# Retro_Watch.net
KiCad netlist of a schematic drawn in EAGLE
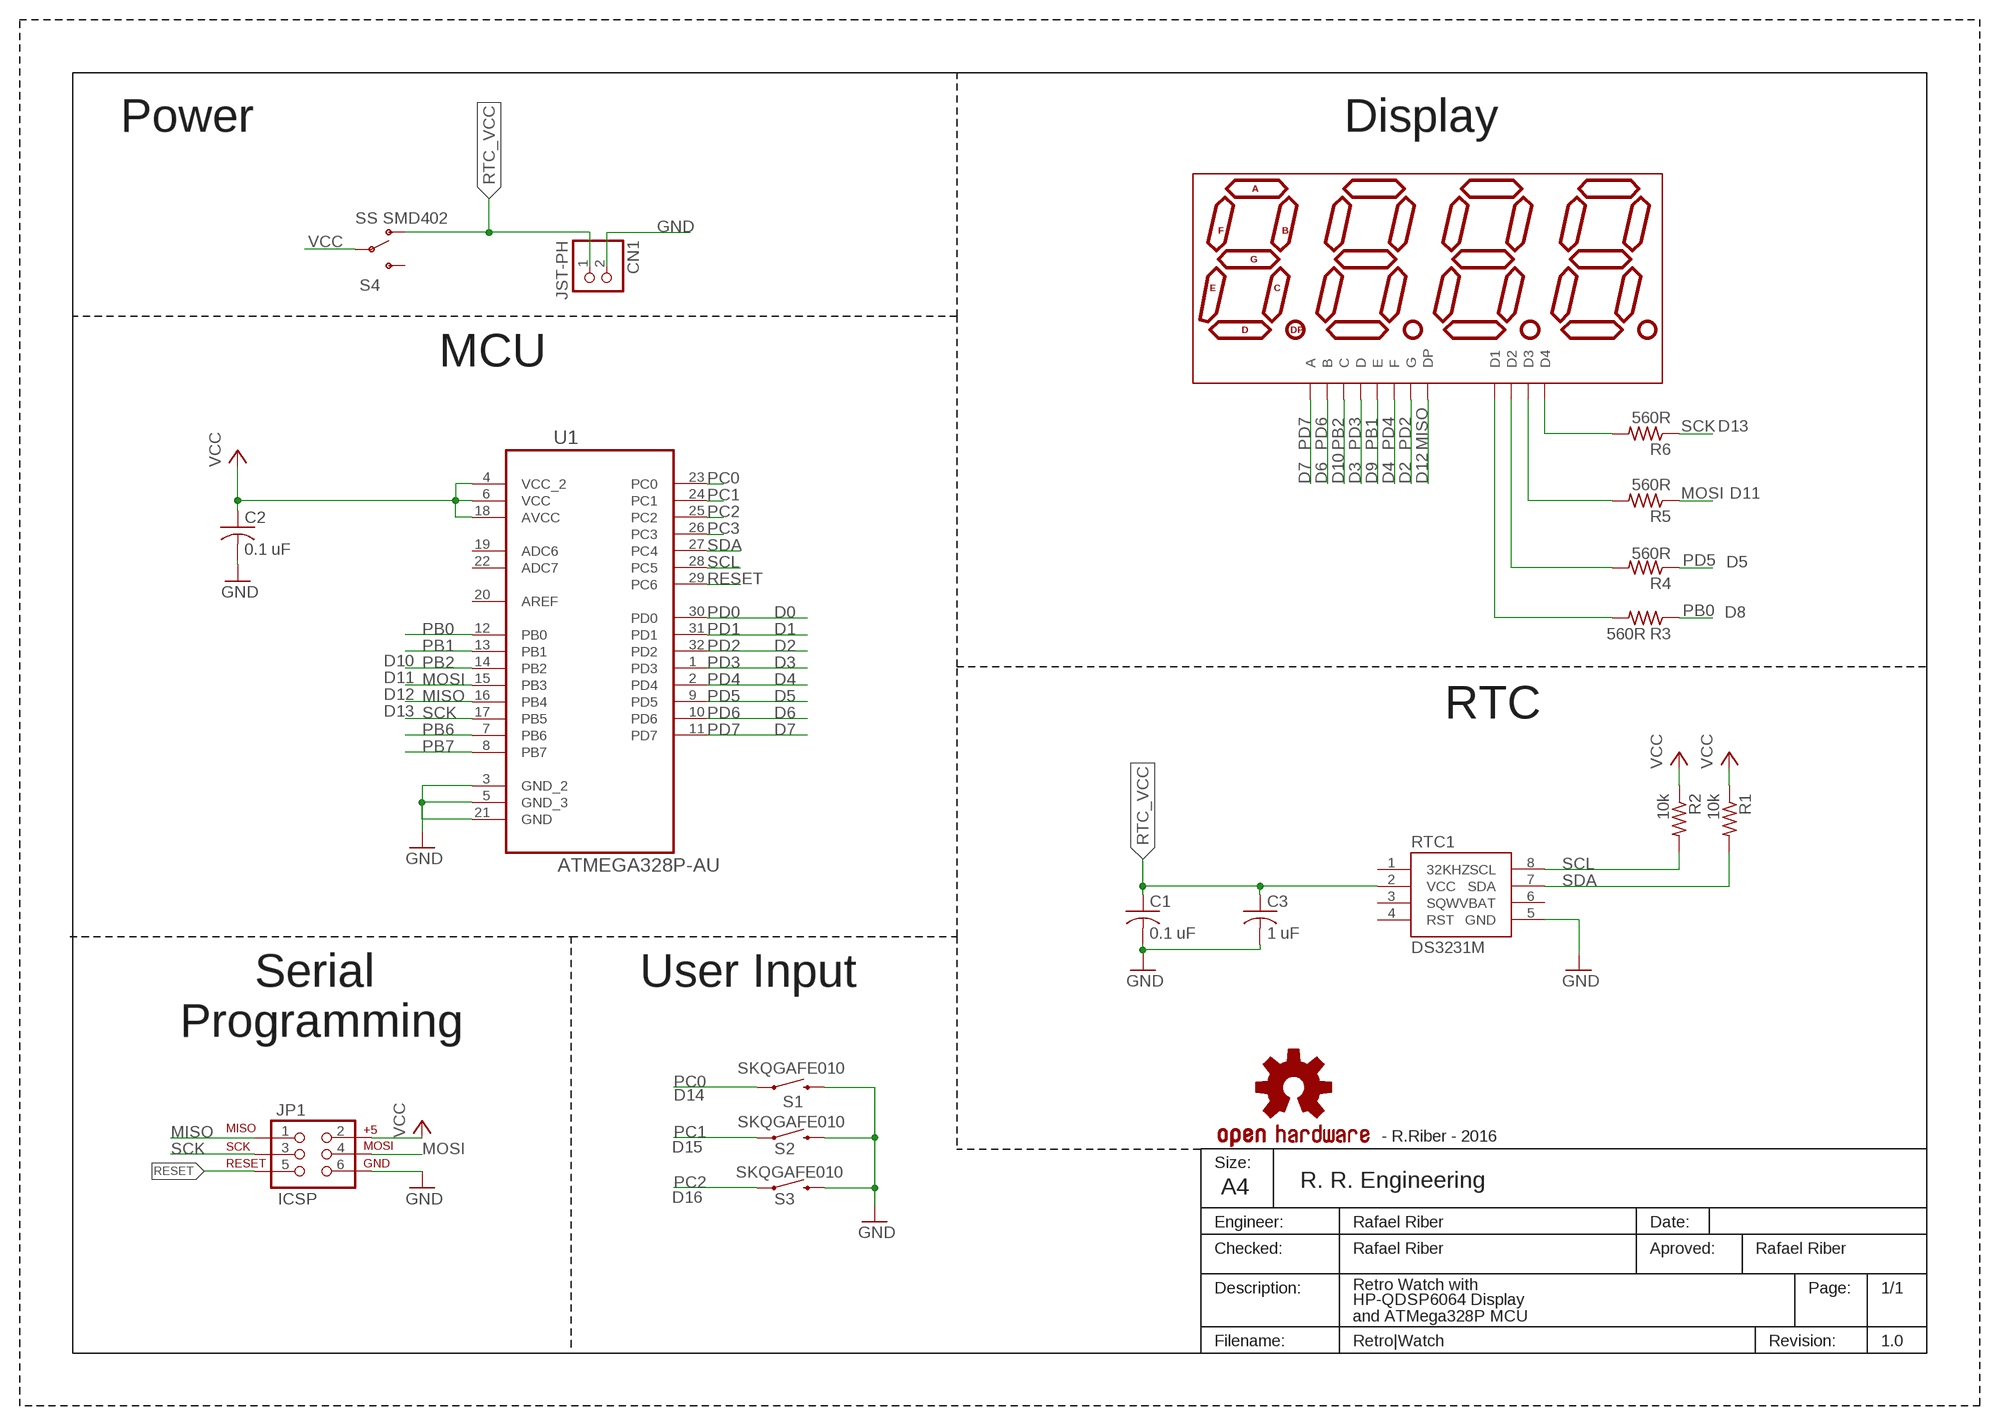
[diagram p0: schematic, sheet 1]

(export (version "E")
  (design (tool "Eeschema 10.0.6"))
  (components
    (comp (ref "C1")
      (value "0.1 uF")
      (footprint "eagle-import:C0805")
      (fields (field (name "MF") "WALSIN") (field (name "MPN") "0805B104K500CT"))
      (libsource (lib "eagle-import") (part "C-USC0805"))
    )
    (comp (ref "C2")
      (value "0.1 uF")
      (footprint "eagle-import:C0805")
      (fields (field (name "MF") "WALSIN") (field (name "MPN") "0805B104K500CT"))
      (libsource (lib "eagle-import") (part "C-USC0805"))
    )
    (comp (ref "C3")
      (value "1 uF")
      (footprint "eagle-import:C0805")
      (libsource (lib "eagle-import") (part "C-USC0805"))
    )
    (comp (ref "CN1")
      (value "JST-PH")
      (footprint "eagle-import:JST-PH-2-SMT-RA")
      (libsource (lib "eagle-import") (part "JST_2PIN-SMT-RA"))
    )
    (comp (ref "DISP1")
      (value "hp")
      (footprint "eagle-import:DIL12")
      (libsource (lib "eagle-import") (part "7-SEGMENT-4DIGIT-COUNTER-HP-BUBBLE"))
    )
    (comp (ref "JP1")
      (value "ICSP")
      (footprint "eagle-import:2X3_LOCK")
      (libsource (lib "eagle-import") (part "AVR_SPI_PRG_62X3_LOCK"))
    )
    (comp (ref "LOGO1")
      (value "OSHW-LOGOM-COPPER")
      (footprint "eagle-import:OSHW-LOGO-M_COPPER")
      (libsource (lib "eagle-import") (part "OSHW-LOGOM-COPPER"))
    )
    (comp (ref "R1")
      (value "10k")
      (footprint "eagle-import:R0805")
      (libsource (lib "eagle-import") (part "R-US_R0805"))
    )
    (comp (ref "R2")
      (value "10k")
      (footprint "eagle-import:R0805")
      (libsource (lib "eagle-import") (part "R-US_R0805"))
    )
    (comp (ref "R3")
      (value "560R")
      (footprint "eagle-import:R0805")
      (libsource (lib "eagle-import") (part "R-US_R0805"))
    )
    (comp (ref "R4")
      (value "560R")
      (footprint "eagle-import:R0805")
      (libsource (lib "eagle-import") (part "R-US_R0805"))
    )
    (comp (ref "R5")
      (value "560R")
      (footprint "eagle-import:R0805")
      (libsource (lib "eagle-import") (part "R-US_R0805"))
    )
    (comp (ref "R6")
      (value "560R")
      (footprint "eagle-import:R0805")
      (libsource (lib "eagle-import") (part "R-US_R0805"))
    )
    (comp (ref "RTC1")
      (value "DS3231M")
      (footprint "eagle-import:SOIC8")
      (libsource (lib "eagle-import") (part "DS3231M"))
    )
    (comp (ref "S1")
      (value "SKQGAFE010")
      (footprint "eagle-import:TACTILE-SWITCH-SMD")
      (libsource (lib "eagle-import") (part "SWITCH-MOMENTARY-2SMD"))
    )
    (comp (ref "S2")
      (value "SKQGAFE010")
      (footprint "eagle-import:TACTILE-SWITCH-SMD")
      (libsource (lib "eagle-import") (part "SWITCH-MOMENTARY-2SMD"))
    )
    (comp (ref "S3")
      (value "SKQGAFE010")
      (footprint "eagle-import:TACTILE-SWITCH-SMD")
      (libsource (lib "eagle-import") (part "SWITCH-MOMENTARY-2SMD"))
    )
    (comp (ref "S4")
      (value "SS SMD402")
      (footprint "eagle-import:SWITCH-SPDT-SMD")
      (libsource (lib "eagle-import") (part "SWITCH-SPDTSMD2"))
    )
    (comp (ref "U1")
      (value "ATMEGA328P-AU")
      (footprint "eagle-import:QFP80P900X900X120-32N")
      (fields (field (name "MF") "ATMEL"))
      (libsource (lib "eagle-import") (part "ATMEGA328P-AU"))
    )
  )
  (nets
    (net (code "1") (name "/MISO") (class "Default")
      (node (ref "DISP1") (pin "5") (pinfunction "DP_5") (pintype "bidirectional"))
      (node (ref "JP1") (pin "1") (pinfunction "1_1") (pintype "passive"))
      (node (ref "U1") (pin "16") (pinfunction "PB4_16") (pintype "bidirectional"))
    )
    (net (code "2") (name "/MOSI") (class "Default")
      (node (ref "JP1") (pin "4") (pinfunction "4_4") (pintype "passive"))
      (node (ref "R5") (pin "1") (pinfunction "1_1") (pintype "passive"))
      (node (ref "U1") (pin "15") (pinfunction "PB3_15") (pintype "bidirectional"))
    )
    (net (code "3") (name "/PB0") (class "Default")
      (node (ref "R3") (pin "1") (pinfunction "1_1") (pintype "passive"))
      (node (ref "U1") (pin "12") (pinfunction "PB0_12") (pintype "bidirectional"))
    )
    (net (code "4") (name "/PB1") (class "Default")
      (node (ref "DISP1") (pin "2") (pinfunction "E_2") (pintype "bidirectional"))
      (node (ref "U1") (pin "13") (pinfunction "PB1_13") (pintype "bidirectional"))
    )
    (net (code "5") (name "/PB2") (class "Default")
      (node (ref "DISP1") (pin "3") (pinfunction "C_3") (pintype "bidirectional"))
      (node (ref "U1") (pin "14") (pinfunction "PB2_14") (pintype "bidirectional"))
    )
    (net (code "6") (name "/PB6") (class "Default")
      (node (ref "U1") (pin "7") (pinfunction "PB6_7") (pintype "bidirectional"))
    )
    (net (code "7") (name "/PB7") (class "Default")
      (node (ref "U1") (pin "8") (pinfunction "PB7_8") (pintype "bidirectional"))
    )
    (net (code "8") (name "/PC0") (class "Default")
      (node (ref "S1") (pin "1") (pinfunction "1_1") (pintype "passive"))
      (node (ref "U1") (pin "23") (pinfunction "PC0_23") (pintype "bidirectional"))
    )
    (net (code "9") (name "/PC1") (class "Default")
      (node (ref "S2") (pin "1") (pinfunction "1_1") (pintype "passive"))
      (node (ref "U1") (pin "24") (pinfunction "PC1_24") (pintype "bidirectional"))
    )
    (net (code "10") (name "/PC2") (class "Default")
      (node (ref "S3") (pin "1") (pinfunction "1_1") (pintype "passive"))
      (node (ref "U1") (pin "25") (pinfunction "PC2_25") (pintype "bidirectional"))
    )
    (net (code "11") (name "/PC3") (class "Default")
      (node (ref "U1") (pin "26") (pinfunction "PC3_26") (pintype "bidirectional"))
    )
    (net (code "12") (name "/PD0") (class "Default")
      (node (ref "U1") (pin "30") (pinfunction "PD0_30") (pintype "bidirectional"))
    )
    (net (code "13") (name "/PD1") (class "Default")
      (node (ref "U1") (pin "31") (pinfunction "PD1_31") (pintype "bidirectional"))
    )
    (net (code "14") (name "/PD2") (class "Default")
      (node (ref "DISP1") (pin "7") (pinfunction "G_7") (pintype "bidirectional"))
      (node (ref "U1") (pin "32") (pinfunction "PD2_32") (pintype "bidirectional"))
    )
    (net (code "15") (name "/PD3") (class "Default")
      (node (ref "DISP1") (pin "8") (pinfunction "D_8") (pintype "bidirectional"))
      (node (ref "U1") (pin "1") (pinfunction "PD3_1") (pintype "bidirectional"))
    )
    (net (code "16") (name "/PD4") (class "Default")
      (node (ref "DISP1") (pin "9") (pinfunction "F_9") (pintype "bidirectional"))
      (node (ref "U1") (pin "2") (pinfunction "PD4_2") (pintype "bidirectional"))
    )
    (net (code "17") (name "/PD5") (class "Default")
      (node (ref "R4") (pin "1") (pinfunction "1_1") (pintype "passive"))
      (node (ref "U1") (pin "9") (pinfunction "PD5_9") (pintype "bidirectional"))
    )
    (net (code "18") (name "/PD6") (class "Default")
      (node (ref "DISP1") (pin "11") (pinfunction "B_11") (pintype "bidirectional"))
      (node (ref "U1") (pin "10") (pinfunction "PD6_10") (pintype "bidirectional"))
    )
    (net (code "19") (name "/PD7") (class "Default")
      (node (ref "DISP1") (pin "12") (pinfunction "A_12") (pintype "bidirectional"))
      (node (ref "U1") (pin "11") (pinfunction "PD7_11") (pintype "bidirectional"))
    )
    (net (code "20") (name "/SCK") (class "Default")
      (node (ref "JP1") (pin "3") (pinfunction "3_3") (pintype "passive"))
      (node (ref "R6") (pin "1") (pinfunction "1_1") (pintype "passive"))
      (node (ref "U1") (pin "17") (pinfunction "PB5_17") (pintype "bidirectional"))
    )
    (net (code "21") (name "/SCL") (class "Default")
      (node (ref "R2") (pin "2") (pinfunction "2_2") (pintype "passive"))
      (node (ref "RTC1") (pin "8") (pinfunction "SCL_8") (pintype "bidirectional"))
      (node (ref "U1") (pin "28") (pinfunction "PC5_28") (pintype "bidirectional"))
    )
    (net (code "22") (name "/SDA") (class "Default")
      (node (ref "R1") (pin "2") (pinfunction "2_2") (pintype "passive"))
      (node (ref "RTC1") (pin "7") (pinfunction "SDA_7") (pintype "bidirectional"))
      (node (ref "U1") (pin "27") (pinfunction "PC4_27") (pintype "bidirectional"))
    )
    (net (code "23") (name "/VBAT") (class "Default")
      (node (ref "RTC1") (pin "6") (pinfunction "VBAT_6") (pintype "power_in"))
    )
    (net (code "24") (name "GND") (class "Default")
      (node (ref "C1") (pin "2") (pinfunction "2_2") (pintype "passive"))
      (node (ref "C2") (pin "2") (pinfunction "2_2") (pintype "passive"))
      (node (ref "C3") (pin "2") (pinfunction "2_2") (pintype "passive"))
      (node (ref "CN1") (pin "2") (pinfunction "1_2") (pintype "passive"))
      (node (ref "JP1") (pin "6") (pinfunction "6_6") (pintype "passive"))
      (node (ref "RTC1") (pin "5") (pinfunction "GND_5") (pintype "power_in"))
      (node (ref "S1") (pin "3") (pinfunction "2_3") (pintype "passive"))
      (node (ref "S2") (pin "3") (pinfunction "2_3") (pintype "passive"))
      (node (ref "S3") (pin "3") (pinfunction "2_3") (pintype "passive"))
      (node (ref "U1") (pin "21") (pinfunction "GND_21") (pintype "passive"))
      (node (ref "U1") (pin "3") (pinfunction "GND_2_3") (pintype "passive"))
      (node (ref "U1") (pin "5") (pinfunction "GND_3_5") (pintype "passive"))
    )
    (net (code "25") (name "Net-(DISP1-D1)") (class "Default")
      (node (ref "DISP1") (pin "1") (pinfunction "D1_1") (pintype "bidirectional"))
      (node (ref "R3") (pin "2") (pinfunction "2_2") (pintype "passive"))
    )
    (net (code "26") (name "Net-(DISP1-D2)") (class "Default")
      (node (ref "DISP1") (pin "10") (pinfunction "D2_10") (pintype "bidirectional"))
      (node (ref "R4") (pin "2") (pinfunction "2_2") (pintype "passive"))
    )
    (net (code "27") (name "Net-(DISP1-D3)") (class "Default")
      (node (ref "DISP1") (pin "4") (pinfunction "D3_4") (pintype "bidirectional"))
      (node (ref "R5") (pin "2") (pinfunction "2_2") (pintype "passive"))
    )
    (net (code "28") (name "Net-(DISP1-D4)") (class "Default")
      (node (ref "DISP1") (pin "6") (pinfunction "D4_6") (pintype "bidirectional"))
      (node (ref "R6") (pin "2") (pinfunction "2_2") (pintype "passive"))
    )
    (net (code "29") (name "RESET") (class "Default")
      (node (ref "JP1") (pin "5") (pinfunction "5_5") (pintype "passive"))
      (node (ref "U1") (pin "29") (pinfunction "PC6_29") (pintype "bidirectional"))
    )
    (net (code "30") (name "RTC_VCC") (class "Default")
      (node (ref "C1") (pin "1") (pinfunction "1_1") (pintype "passive"))
      (node (ref "C3") (pin "1") (pinfunction "1_1") (pintype "passive"))
      (node (ref "CN1") (pin "1") (pinfunction "2_1") (pintype "passive"))
      (node (ref "RTC1") (pin "2") (pinfunction "VCC_2") (pintype "power_in"))
      (node (ref "S4") (pin "1") (pinfunction "O_1") (pintype "passive"))
    )
    (net (code "31") (name "VCC") (class "Default")
      (node (ref "C2") (pin "1") (pinfunction "1_1") (pintype "passive"))
      (node (ref "JP1") (pin "2") (pinfunction "2_2") (pintype "passive"))
      (node (ref "R1") (pin "1") (pinfunction "1_1") (pintype "passive"))
      (node (ref "R2") (pin "1") (pinfunction "1_1") (pintype "passive"))
      (node (ref "S4") (pin "2") (pinfunction "P_2") (pintype "passive"))
      (node (ref "U1") (pin "18") (pinfunction "AVCC_18") (pintype "power_in"))
      (node (ref "U1") (pin "4") (pinfunction "VCC_2_4") (pintype "power_in"))
      (node (ref "U1") (pin "6") (pinfunction "VCC_6") (pintype "power_in"))
    )
    (net (code "32") (name "unconnected-(RTC1-32KHZ-Pad1)") (class "Default")
      (node (ref "RTC1") (pin "1") (pinfunction "32KHZ_1") (pintype "output"))
    )
    (net (code "33") (name "unconnected-(RTC1-RST-Pad4)") (class "Default")
      (node (ref "RTC1") (pin "4") (pinfunction "RST_4") (pintype "bidirectional"))
    )
    (net (code "34") (name "unconnected-(RTC1-SQW-Pad3)") (class "Default")
      (node (ref "RTC1") (pin "3") (pinfunction "SQW_3") (pintype "output"))
    )
    (net (code "35") (name "unconnected-(S4-S-Pad3)") (class "Default")
      (node (ref "S4") (pin "3") (pinfunction "S_3") (pintype "passive"))
    )
    (net (code "36") (name "unconnected-(U1-ADC6-Pad19)") (class "Default")
      (node (ref "U1") (pin "19") (pinfunction "ADC6_19") (pintype "input"))
    )
    (net (code "37") (name "unconnected-(U1-ADC7-Pad22)") (class "Default")
      (node (ref "U1") (pin "22") (pinfunction "ADC7_22") (pintype "input"))
    )
    (net (code "38") (name "unconnected-(U1-AREF-Pad20)") (class "Default")
      (node (ref "U1") (pin "20") (pinfunction "AREF_20") (pintype "input"))
    )
  )
)
